# MPPT_CC_CV_charger_B.net
KiCad netlist of a schematic drawn in Altium Designer
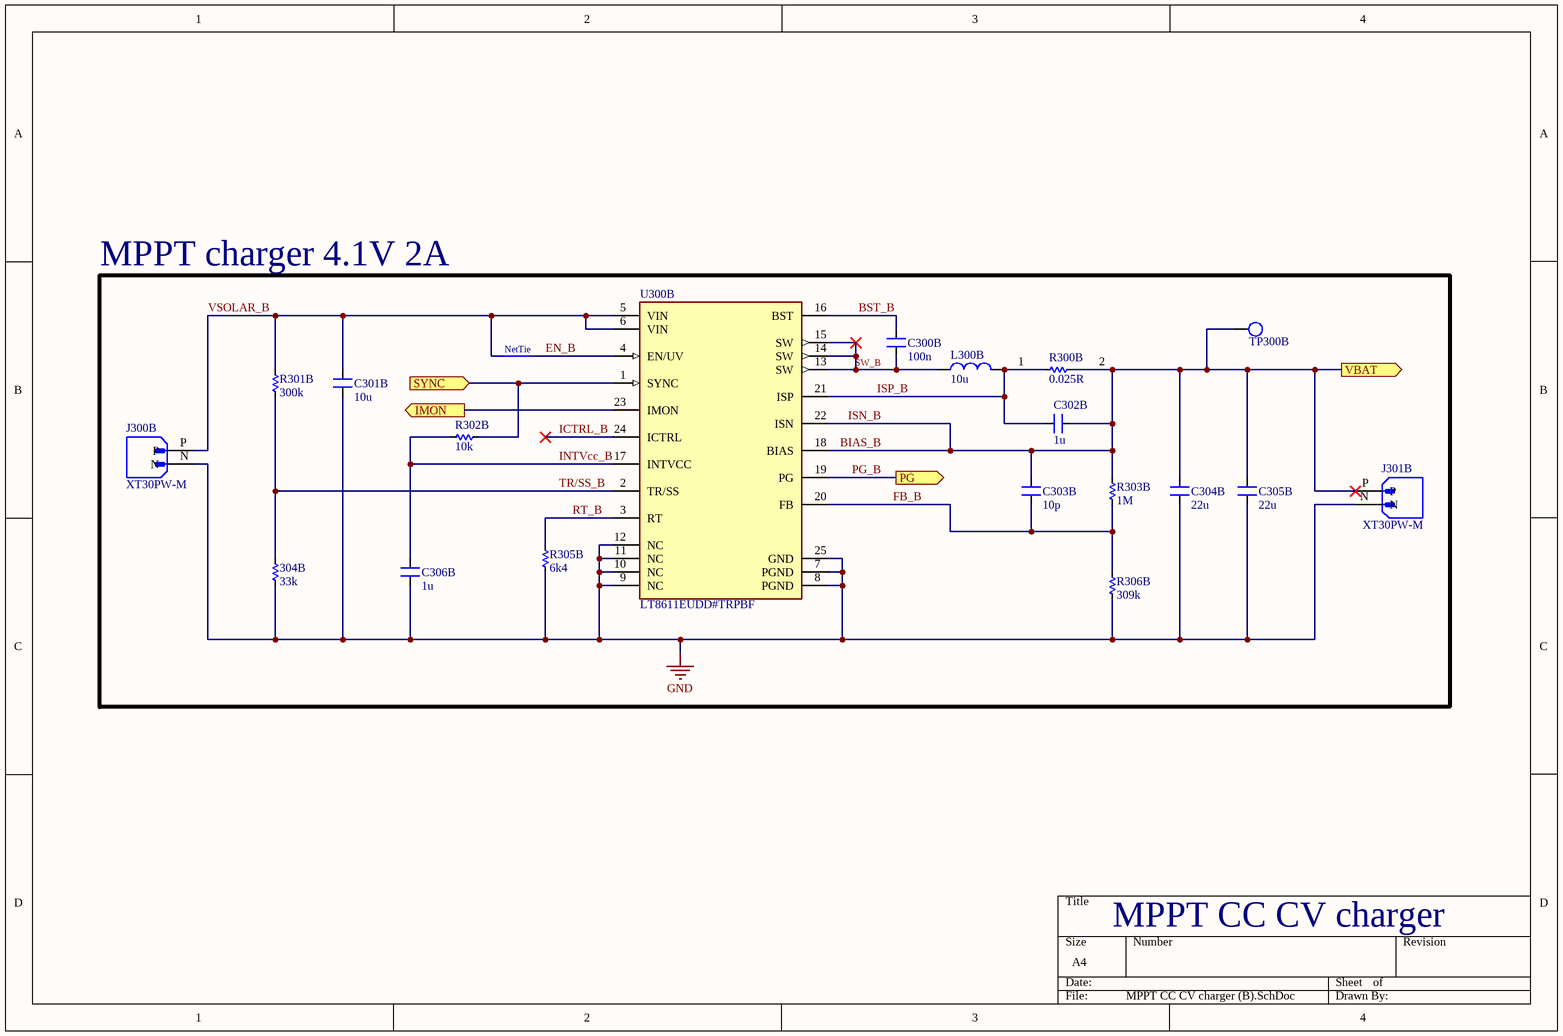
[diagram p0: MPPT CC CV charger (B).SchDoc]

(export (version "E")
  (design (tool "Eeschema 10.0.6"))
  (components
    (comp (ref "304B")
      (value "33k")
      (footprint "RES-SMD-0603")
      (description "Resistor")
      (fields
        (field (name "MANUFACTURER") "Generic Components")
        (field (name "PUBLISHER") "Altium Hobart Technology Centre")
      )
      (libsource (lib "Library") (part "Res-SMD"))
    )
    (comp (ref "C300B") (value "100n") (footprint "CN-SMD-0603") (libsource (lib "Library") (part "CN")))
    (comp (ref "C301B") (value "10u") (footprint "CN-SMD-0603") (libsource (lib "Library") (part "CN")))
    (comp (ref "C302B") (value "1u") (footprint "CN-SMD-0603") (libsource (lib "Library") (part "CN")))
    (comp (ref "C303B") (value "10p") (footprint "CN-SMD-0603") (libsource (lib "Library") (part "CN")))
    (comp (ref "C304B") (value "22u") (footprint "CN-SMD-0603") (libsource (lib "Library") (part "CN")))
    (comp (ref "C305B") (value "22u") (footprint "CN-SMD-0603") (libsource (lib "Library") (part "CN")))
    (comp (ref "C306B") (value "1u") (footprint "CN-SMD-0603") (libsource (lib "Library") (part "CN")))
    (comp (ref "J300B")
      (value "XT30PW-M")
      (footprint "AMASS_XT30PW-M")
      (description "Socket; DC supply; XT30; male; PIN: 2; on PCBs; THT; Colour: yellow")
      (fields (field (name "MF") "AMASS"))
      (libsource (lib "") (part "XT30PW-M_1"))
    )
    (comp (ref "J301B")
      (value "XT30PW-M")
      (footprint "AMASS_XT30PW-M")
      (description "Socket; DC supply; XT30; male; PIN: 2; on PCBs; THT; Colour: yellow")
      (fields (field (name "MF") "AMASS"))
      (libsource (lib "XT30PW-M") (part "XT30PW-M"))
    )
    (comp (ref "L300B")
      (value "10u")
      (footprint "L-SMD-M-7.3x4.5")
      (fields
        (field (name "PARTNO") "78477010")
        (field (name "MANUFACTURER") "Wurth Elektronik")
        (field (name "CREATED BY") "Baojun Chen")
      )
      (libsource (lib "Library") (part "L-SMD-1"))
    )
    (comp (ref "R300B")
      (value "0.025R")
      (footprint "RES-SMD-0603")
      (description "Resistor")
      (fields
        (field (name "MANUFACTURER") "Generic Components")
        (field (name "PUBLISHER") "Altium Hobart Technology Centre")
      )
      (libsource (lib "Library") (part "Res-SMD"))
    )
    (comp (ref "R301B")
      (value "300k")
      (footprint "RES-SMD-0603")
      (description "Resistor")
      (fields
        (field (name "MANUFACTURER") "Generic Components")
        (field (name "PUBLISHER") "Altium Hobart Technology Centre")
      )
      (libsource (lib "Library") (part "Res-SMD"))
    )
    (comp (ref "R302B")
      (value "10k")
      (footprint "RES-SMD-0603")
      (description "Resistor")
      (fields
        (field (name "MANUFACTURER") "Generic Components")
        (field (name "PUBLISHER") "Altium Hobart Technology Centre")
      )
      (libsource (lib "Library") (part "Res-SMD"))
    )
    (comp (ref "R303B")
      (value "1M")
      (footprint "RES-SMD-0603")
      (description "Resistor")
      (fields
        (field (name "MANUFACTURER") "Generic Components")
        (field (name "PUBLISHER") "Altium Hobart Technology Centre")
      )
      (libsource (lib "Library") (part "Res-SMD"))
    )
    (comp (ref "R305B")
      (value "6k4")
      (footprint "RES-SMD-0603")
      (description "Resistor")
      (fields
        (field (name "MANUFACTURER") "Generic Components")
        (field (name "PUBLISHER") "Altium Hobart Technology Centre")
      )
      (libsource (lib "Library") (part "Res-SMD"))
    )
    (comp (ref "R306B")
      (value "309k")
      (footprint "RES-SMD-0603")
      (description "Resistor")
      (fields
        (field (name "MANUFACTURER") "Generic Components")
        (field (name "PUBLISHER") "Altium Hobart Technology Centre")
      )
      (libsource (lib "Library") (part "Res-SMD"))
    )
    (comp (ref "TP300B")
      (value "Test-Point")
      (footprint "TESTPOINT")
      (libsource (lib "Library") (part "Test-Point"))
    )
    (comp (ref "U300B")
      (value "LT8611EUDD#TRPBF")
      (footprint "FP-UDD-24-05-08-1833-IPC_B")
      (description "IC REG BUCK ADJ 2.5A 24QFN")
      (libsource (lib "Altium Content Vault") (part "fa917c90ce6974f84498b26f3756de5"))
    )
  )
  (nets
    (net (code "1") (name "/BIAS_B") (class "Default")
      (node (ref "C302B") (pin "2") (pinfunction "2_2") (pintype "passive"))
      (node (ref "C303B") (pin "2") (pinfunction "2_2") (pintype "passive"))
      (node (ref "C304B") (pin "2") (pinfunction "2_2") (pintype "passive"))
      (node (ref "C305B") (pin "2") (pinfunction "2_2") (pintype "passive"))
      (node (ref "J301B") (pin "P") (pinfunction "P_P") (pintype "power_in"))
      (node (ref "R300B") (pin "1") (pinfunction "1_1") (pintype "passive"))
      (node (ref "R303B") (pin "1") (pinfunction "1_1") (pintype "passive"))
      (node (ref "TP300B") (pin "1") (pinfunction "1_1") (pintype "passive"))
      (node (ref "U300B") (pin "18") (pinfunction "BIAS_18") (pintype "passive"))
      (node (ref "U300B") (pin "22") (pinfunction "ISN_22") (pintype "passive"))
    )
    (net (code "2") (name "/BST_B") (class "Default")
      (node (ref "C300B") (pin "2") (pinfunction "2_2") (pintype "passive"))
      (node (ref "U300B") (pin "16") (pinfunction "BST_16") (pintype "passive"))
    )
    (net (code "3") (name "/EN_B") (class "Default")
      (node (ref "C301B") (pin "2") (pinfunction "2_2") (pintype "passive"))
      (node (ref "J300B") (pin "P") (pinfunction "P_P") (pintype "power_in"))
      (node (ref "R301B") (pin "2") (pinfunction "2_2") (pintype "passive"))
      (node (ref "U300B") (pin "4") (pinfunction "EN/UV_4") (pintype "input"))
      (node (ref "U300B") (pin "5") (pinfunction "VIN_5") (pintype "power_in"))
      (node (ref "U300B") (pin "6") (pinfunction "VIN_6") (pintype "power_in"))
    )
    (net (code "4") (name "/FB_B") (class "Default")
      (node (ref "C303B") (pin "1") (pinfunction "1_1") (pintype "passive"))
      (node (ref "R303B") (pin "2") (pinfunction "2_2") (pintype "passive"))
      (node (ref "R306B") (pin "1") (pinfunction "1_1") (pintype "passive"))
      (node (ref "U300B") (pin "20") (pinfunction "FB_20") (pintype "passive"))
    )
    (net (code "5") (name "/ICTRL_B") (class "Default")
      (node (ref "U300B") (pin "24") (pinfunction "ICTRL_24") (pintype "passive+no_connect"))
    )
    (net (code "6") (name "/IMON") (class "Default")
      (node (ref "U300B") (pin "23") (pinfunction "IMON_23") (pintype "passive"))
    )
    (net (code "7") (name "/INTVcc_B") (class "Default")
      (node (ref "C306B") (pin "2") (pinfunction "2_2") (pintype "passive"))
      (node (ref "R302B") (pin "2") (pinfunction "2_2") (pintype "passive"))
      (node (ref "U300B") (pin "17") (pinfunction "INTVCC_17") (pintype "passive"))
    )
    (net (code "8") (name "/ISP_B") (class "Default")
      (node (ref "C302B") (pin "1") (pinfunction "1_1") (pintype "passive"))
      (node (ref "L300B") (pin "2") (pinfunction "2_2") (pintype "passive"))
      (node (ref "R300B") (pin "2") (pinfunction "2_2") (pintype "passive"))
      (node (ref "U300B") (pin "21") (pinfunction "ISP_21") (pintype "passive"))
    )
    (net (code "9") (name "/PG_B") (class "Default")
      (node (ref "U300B") (pin "19") (pinfunction "PG_19") (pintype "passive"))
    )
    (net (code "10") (name "/RT_B") (class "Default")
      (node (ref "R305B") (pin "2") (pinfunction "2_2") (pintype "passive"))
      (node (ref "U300B") (pin "3") (pinfunction "RT_3") (pintype "passive"))
    )
    (net (code "11") (name "/SW_B") (class "Default")
      (node (ref "C300B") (pin "1") (pinfunction "1_1") (pintype "passive"))
      (node (ref "L300B") (pin "1") (pinfunction "1_1") (pintype "passive"))
      (node (ref "U300B") (pin "13") (pinfunction "SW_13") (pintype "output"))
      (node (ref "U300B") (pin "14") (pinfunction "SW_14") (pintype "output"))
      (node (ref "U300B") (pin "15") (pinfunction "SW_15") (pintype "output"))
    )
    (net (code "12") (name "/SYNC") (class "Default")
      (node (ref "R302B") (pin "1") (pinfunction "1_1") (pintype "passive"))
      (node (ref "U300B") (pin "1") (pinfunction "SYNC_1") (pintype "input"))
    )
    (net (code "13") (name "/TR{slash}SS_B") (class "Default")
      (node (ref "304B") (pin "2") (pinfunction "2_2") (pintype "passive"))
      (node (ref "R301B") (pin "1") (pinfunction "1_1") (pintype "passive"))
      (node (ref "U300B") (pin "2") (pinfunction "TR/SS_2") (pintype "passive"))
    )
    (net (code "14") (name "GND") (class "Default")
      (node (ref "304B") (pin "1") (pinfunction "1_1") (pintype "passive"))
      (node (ref "C301B") (pin "1") (pinfunction "1_1") (pintype "passive"))
      (node (ref "C304B") (pin "1") (pinfunction "1_1") (pintype "passive"))
      (node (ref "C305B") (pin "1") (pinfunction "1_1") (pintype "passive"))
      (node (ref "C306B") (pin "1") (pinfunction "1_1") (pintype "passive"))
      (node (ref "J300B") (pin "N") (pinfunction "N_N") (pintype "power_in"))
      (node (ref "J301B") (pin "N") (pinfunction "N_N") (pintype "power_in"))
      (node (ref "R305B") (pin "1") (pinfunction "1_1") (pintype "passive"))
      (node (ref "R306B") (pin "2") (pinfunction "2_2") (pintype "passive"))
      (node (ref "U300B") (pin "10") (pinfunction "NC_10") (pintype "passive"))
      (node (ref "U300B") (pin "11") (pinfunction "NC_11") (pintype "passive"))
      (node (ref "U300B") (pin "12") (pinfunction "NC_12") (pintype "passive"))
      (node (ref "U300B") (pin "25") (pinfunction "GND_25") (pintype "power_in"))
      (node (ref "U300B") (pin "7") (pinfunction "PGND_7") (pintype "power_in"))
      (node (ref "U300B") (pin "8") (pinfunction "PGND_8") (pintype "power_in"))
      (node (ref "U300B") (pin "9") (pinfunction "NC_9") (pintype "passive"))
    )
  )
)
